# Power.net
KiCad netlist of a schematic drawn in Altium Designer
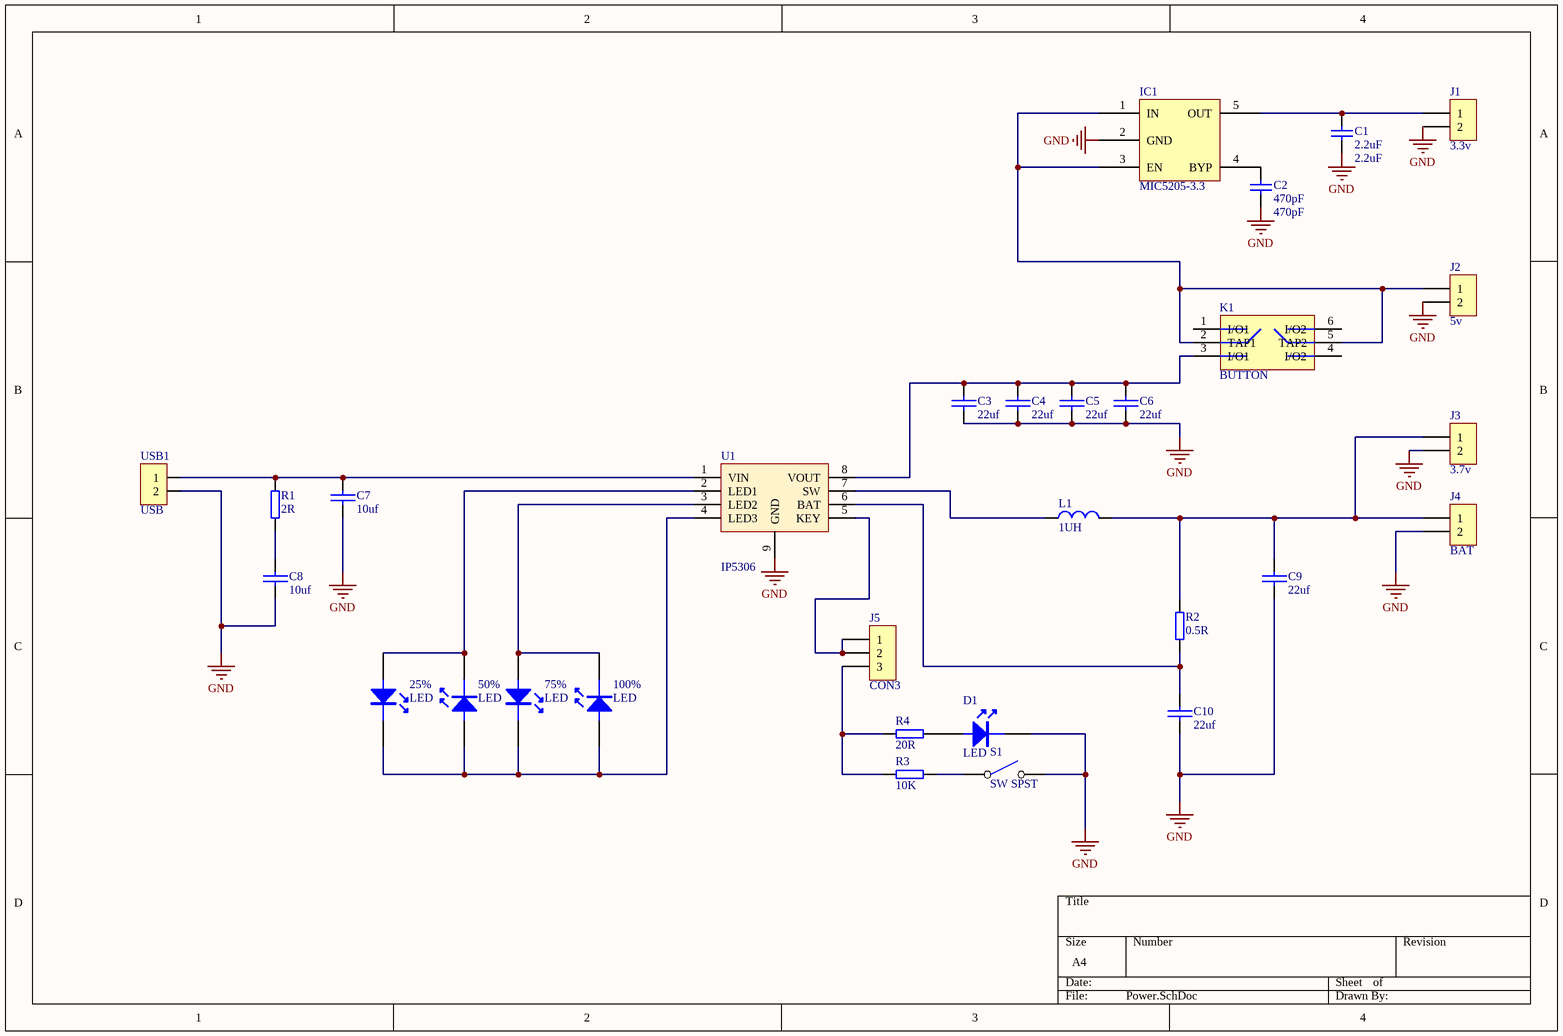
[diagram p0: Power.SchDoc]

(export (version "E")
  (design (tool "Eeschema 10.0.6"))
  (components
    (comp (ref "25%") (value "LED") (footprint "6-0805_L") (libsource (lib "杂元件库") (part "LED")))
    (comp (ref "50%") (value "LED") (footprint "6-0805_L") (libsource (lib "杂元件库") (part "LED")))
    (comp (ref "75%") (value "LED") (footprint "6-0805_L") (libsource (lib "杂元件库") (part "LED")))
    (comp (ref "100%") (value "LED") (footprint "6-0805_L") (libsource (lib "杂元件库") (part "LED")))
    (comp (ref "C1")
      (value "2.2uF")
      (footprint "6-0805_L")
      (description "Capacitor (Semiconductor SIM Model)")
      (fields (field (name "ALTIUM_VALUE") "2.2uF") (field (name "PUBLISHER") "Altium Limited"))
      (libsource (lib "Miscellaneous Devices") (part "Cap Semi"))
    )
    (comp (ref "C2")
      (value "470pF")
      (footprint "6-0805_L")
      (description "Capacitor (Semiconductor SIM Model)")
      (fields (field (name "ALTIUM_VALUE") "470pF") (field (name "PUBLISHER") "Altium Limited"))
      (libsource (lib "Miscellaneous Devices") (part "Cap Semi"))
    )
    (comp (ref "C3")
      (value "22uf")
      (footprint "6-0805_L")
      (description "电容")
      (libsource (lib "Component") (part "CAP"))
    )
    (comp (ref "C4")
      (value "22uf")
      (footprint "6-0805_L")
      (description "电容")
      (libsource (lib "Component") (part "CAP"))
    )
    (comp (ref "C5")
      (value "22uf")
      (footprint "6-0805_L")
      (description "电容")
      (libsource (lib "Component") (part "CAP"))
    )
    (comp (ref "C6")
      (value "22uf")
      (footprint "6-0805_L")
      (description "电容")
      (libsource (lib "Component") (part "CAP"))
    )
    (comp (ref "C7")
      (value "10uf")
      (footprint "6-0805_L")
      (description "电容")
      (libsource (lib "Component") (part "CAP"))
    )
    (comp (ref "C8")
      (value "10uf")
      (footprint "6-0805_L")
      (description "电容")
      (libsource (lib "Component") (part "CAP"))
    )
    (comp (ref "C9")
      (value "22uf")
      (footprint "6-0805_L")
      (description "电容")
      (libsource (lib "Component") (part "CAP"))
    )
    (comp (ref "C10")
      (value "22uf")
      (footprint "6-0805_L")
      (description "电容")
      (libsource (lib "Component") (part "CAP"))
    )
    (comp (ref "D1") (value "LED") (footprint "6-0805_L") (libsource (lib "杂元件库") (part "LED")))
    (comp (ref "IC1")
      (value "MIC5205-3.3")
      (footprint "SOT-23-5")
      (description "稳压")
      (libsource (lib "Chip") (part "MIC5205-3.3"))
    )
    (comp (ref "J1")
      (value "3.3v")
      (footprint "HDR1X2")
      (description "连接器")
      (libsource (lib "Connector") (part "CON2"))
    )
    (comp (ref "J2")
      (value "5v")
      (footprint "HDR1X2")
      (description "连接器")
      (libsource (lib "Connector") (part "CON2"))
    )
    (comp (ref "J3")
      (value "3.7v")
      (footprint "HDR1X2")
      (description "连接器")
      (libsource (lib "Connector") (part "CON2"))
    )
    (comp (ref "J4")
      (value "BAT")
      (footprint "接线座2P")
      (description "连接器")
      (libsource (lib "Connector") (part "CON2"))
    )
    (comp (ref "J5")
      (value "CON3")
      (footprint "HDR1X3")
      (description "连接器")
      (libsource (lib "Connector") (part "CON3"))
    )
    (comp (ref "K1")
      (value "BUTTON")
      (footprint "My:switch")
      (description "自锁按键")
      (libsource (lib "Component") (part "BUTTON"))
    )
    (comp (ref "L1")
      (value "1UH")
      (footprint "0630电感")
      (description "电感")
      (libsource (lib "Component") (part "Inductor"))
    )
    (comp (ref "R1")
      (value "2R")
      (footprint "6-0805_L")
      (description "电阻")
      (libsource (lib "Component") (part "RES"))
    )
    (comp (ref "R2")
      (value "0.5R")
      (footprint "6-0805_L")
      (description "电阻")
      (libsource (lib "Component") (part "RES"))
    )
    (comp (ref "R3")
      (value "10K")
      (footprint "6-0805_L")
      (description "电阻")
      (libsource (lib "Component") (part "RES"))
    )
    (comp (ref "R4")
      (value "20R")
      (footprint "6-0805_L")
      (description "电阻")
      (libsource (lib "Component") (part "RES"))
    )
    (comp (ref "S1") (value "SW SPST") (footprint "button") (libsource (lib "杂元件库") (part "SW SPST")))
    (comp (ref "U1") (value "IP5306") (footprint "ESOP8") (libsource (lib "My") (part "IP5306")))
    (comp (ref "USB1")
      (value "USB")
      (footprint "Type-C")
      (description "Conjunctor")
      (libsource (lib "zj") (part "CON2"))
    )
  )
  (nets
    (net (code "1") (name "GND") (class "Default")
      (node (ref "C1") (pin "1") (pinfunction "1_1") (pintype "passive"))
      (node (ref "C10") (pin "2") (pinfunction "2_2") (pintype "passive"))
      (node (ref "C2") (pin "1") (pinfunction "1_1") (pintype "passive"))
      (node (ref "C3") (pin "2") (pinfunction "2_2") (pintype "passive"))
      (node (ref "C4") (pin "2") (pinfunction "2_2") (pintype "passive"))
      (node (ref "C5") (pin "2") (pinfunction "2_2") (pintype "passive"))
      (node (ref "C6") (pin "2") (pinfunction "2_2") (pintype "passive"))
      (node (ref "C7") (pin "2") (pinfunction "2_2") (pintype "passive"))
      (node (ref "C8") (pin "2") (pinfunction "2_2") (pintype "passive"))
      (node (ref "C9") (pin "2") (pinfunction "2_2") (pintype "passive"))
      (node (ref "D1") (pin "K") (pinfunction "2_K") (pintype "passive"))
      (node (ref "IC1") (pin "2") (pinfunction "GND_2") (pintype "passive"))
      (node (ref "J1") (pin "2") (pinfunction "2_2") (pintype "passive"))
      (node (ref "J2") (pin "2") (pinfunction "2_2") (pintype "passive"))
      (node (ref "J3") (pin "2") (pinfunction "2_2") (pintype "passive"))
      (node (ref "J4") (pin "2") (pinfunction "2_2") (pintype "passive"))
      (node (ref "S1") (pin "2") (pinfunction "NO_2") (pintype "passive"))
      (node (ref "U1") (pin "9") (pinfunction "GND_9") (pintype "passive"))
      (node (ref "USB1") (pin "2") (pinfunction "2_2") (pintype "passive"))
    )
    (net (code "2") (name "Net-(25%-1)") (class "Default")
      (node (ref "25%") (pin "A") (pinfunction "1_A") (pintype "passive"))
      (node (ref "50%") (pin "K") (pinfunction "2_K") (pintype "passive"))
      (node (ref "U1") (pin "2") (pinfunction "LED1_2") (pintype "passive"))
    )
    (net (code "3") (name "Net-(100%-1)") (class "Default")
      (node (ref "100%") (pin "A") (pinfunction "1_A") (pintype "passive"))
      (node (ref "25%") (pin "K") (pinfunction "2_K") (pintype "passive"))
      (node (ref "50%") (pin "A") (pinfunction "1_A") (pintype "passive"))
      (node (ref "75%") (pin "K") (pinfunction "2_K") (pintype "passive"))
      (node (ref "U1") (pin "4") (pinfunction "LED3_4") (pintype "passive"))
    )
    (net (code "4") (name "Net-(100%-2)") (class "Default")
      (node (ref "100%") (pin "K") (pinfunction "2_K") (pintype "passive"))
      (node (ref "75%") (pin "A") (pinfunction "1_A") (pintype "passive"))
      (node (ref "U1") (pin "3") (pinfunction "LED2_3") (pintype "passive"))
    )
    (net (code "5") (name "Net-(C8-Pad1)") (class "Default")
      (node (ref "C8") (pin "1") (pinfunction "1_1") (pintype "passive"))
      (node (ref "R1") (pin "1") (pinfunction "1_1") (pintype "passive"))
    )
    (net (code "6") (name "Net-(C9-Pad1)") (class "Default")
      (node (ref "C9") (pin "1") (pinfunction "1_1") (pintype "passive"))
      (node (ref "J3") (pin "1") (pinfunction "1_1") (pintype "passive"))
      (node (ref "J4") (pin "1") (pinfunction "1_1") (pintype "passive"))
      (node (ref "L1") (pin "2") (pinfunction "2_2") (pintype "passive"))
      (node (ref "R2") (pin "1") (pinfunction "1_1") (pintype "passive"))
    )
    (net (code "7") (name "Net-(D1-1)") (class "Default")
      (node (ref "D1") (pin "A") (pinfunction "1_A") (pintype "passive"))
      (node (ref "R4") (pin "1") (pinfunction "1_1") (pintype "passive"))
    )
    (net (code "8") (name "Net-(IC1-BYP)") (class "Default")
      (node (ref "C2") (pin "2") (pinfunction "2_2") (pintype "passive"))
      (node (ref "IC1") (pin "4") (pinfunction "BYP_4") (pintype "passive"))
    )
    (net (code "9") (name "Net-(IC1-EN)") (class "Default")
      (node (ref "IC1") (pin "1") (pinfunction "IN_1") (pintype "passive"))
      (node (ref "IC1") (pin "3") (pinfunction "EN_3") (pintype "passive"))
      (node (ref "J2") (pin "1") (pinfunction "1_1") (pintype "passive"))
      (node (ref "K1") (pin "2") (pinfunction "TAP1_2") (pintype "passive"))
      (node (ref "K1") (pin "5") (pinfunction "TAP2_5") (pintype "passive"))
    )
    (net (code "10") (name "Net-(IC1-OUT)") (class "Default")
      (node (ref "C1") (pin "2") (pinfunction "2_2") (pintype "passive"))
      (node (ref "IC1") (pin "5") (pinfunction "OUT_5") (pintype "passive"))
      (node (ref "J1") (pin "1") (pinfunction "1_1") (pintype "passive"))
    )
    (net (code "11") (name "Net-(J5-Pad3)") (class "Default")
      (node (ref "J5") (pin "3") (pinfunction "3_3") (pintype "passive"))
      (node (ref "R3") (pin "2") (pinfunction "2_2") (pintype "passive"))
      (node (ref "R4") (pin "2") (pinfunction "2_2") (pintype "passive"))
    )
    (net (code "12") (name "Net-(S1-COMMON)") (class "Default")
      (node (ref "R3") (pin "1") (pinfunction "1_1") (pintype "passive"))
      (node (ref "S1") (pin "1") (pinfunction "COMMON_1") (pintype "passive"))
    )
    (net (code "13") (name "Net-(U1-BAT)") (class "Default")
      (node (ref "C10") (pin "1") (pinfunction "1_1") (pintype "passive"))
      (node (ref "R2") (pin "2") (pinfunction "2_2") (pintype "passive"))
      (node (ref "U1") (pin "6") (pinfunction "BAT_6") (pintype "passive"))
    )
    (net (code "14") (name "Net-(U1-KEY)") (class "Default")
      (node (ref "J5") (pin "1") (pinfunction "1_1") (pintype "passive"))
      (node (ref "J5") (pin "2") (pinfunction "2_2") (pintype "passive"))
      (node (ref "U1") (pin "5") (pinfunction "KEY_5") (pintype "passive"))
    )
    (net (code "15") (name "Net-(U1-SW)") (class "Default")
      (node (ref "L1") (pin "1") (pinfunction "1_1") (pintype "passive"))
      (node (ref "U1") (pin "7") (pinfunction "SW_7") (pintype "passive"))
    )
    (net (code "16") (name "Net-(U1-VIN)") (class "Default")
      (node (ref "C7") (pin "1") (pinfunction "1_1") (pintype "passive"))
      (node (ref "R1") (pin "2") (pinfunction "2_2") (pintype "passive"))
      (node (ref "U1") (pin "1") (pinfunction "VIN_1") (pintype "passive"))
      (node (ref "USB1") (pin "1") (pinfunction "1_1") (pintype "passive"))
    )
    (net (code "17") (name "Net-(U1-VOUT)") (class "Default")
      (node (ref "C3") (pin "1") (pinfunction "1_1") (pintype "passive"))
      (node (ref "C4") (pin "1") (pinfunction "1_1") (pintype "passive"))
      (node (ref "C5") (pin "1") (pinfunction "1_1") (pintype "passive"))
      (node (ref "C6") (pin "1") (pinfunction "1_1") (pintype "passive"))
      (node (ref "K1") (pin "3") (pinfunction "I/O1_3") (pintype "passive"))
      (node (ref "U1") (pin "8") (pinfunction "VOUT_8") (pintype "passive"))
    )
    (net (code "18") (name "unconnected-(K1-I{slash}O1-Pad1)") (class "Default")
      (node (ref "K1") (pin "1") (pinfunction "I/O1_1") (pintype "passive"))
    )
    (net (code "19") (name "unconnected-(K1-I{slash}O2-Pad4)") (class "Default")
      (node (ref "K1") (pin "4") (pinfunction "I/O2_4") (pintype "passive"))
    )
    (net (code "20") (name "unconnected-(K1-I{slash}O2-Pad6)") (class "Default")
      (node (ref "K1") (pin "6") (pinfunction "I/O2_6") (pintype "passive"))
    )
  )
)
